# ST1-1-Top.net
KiCad netlist of a schematic drawn in Altium Designer
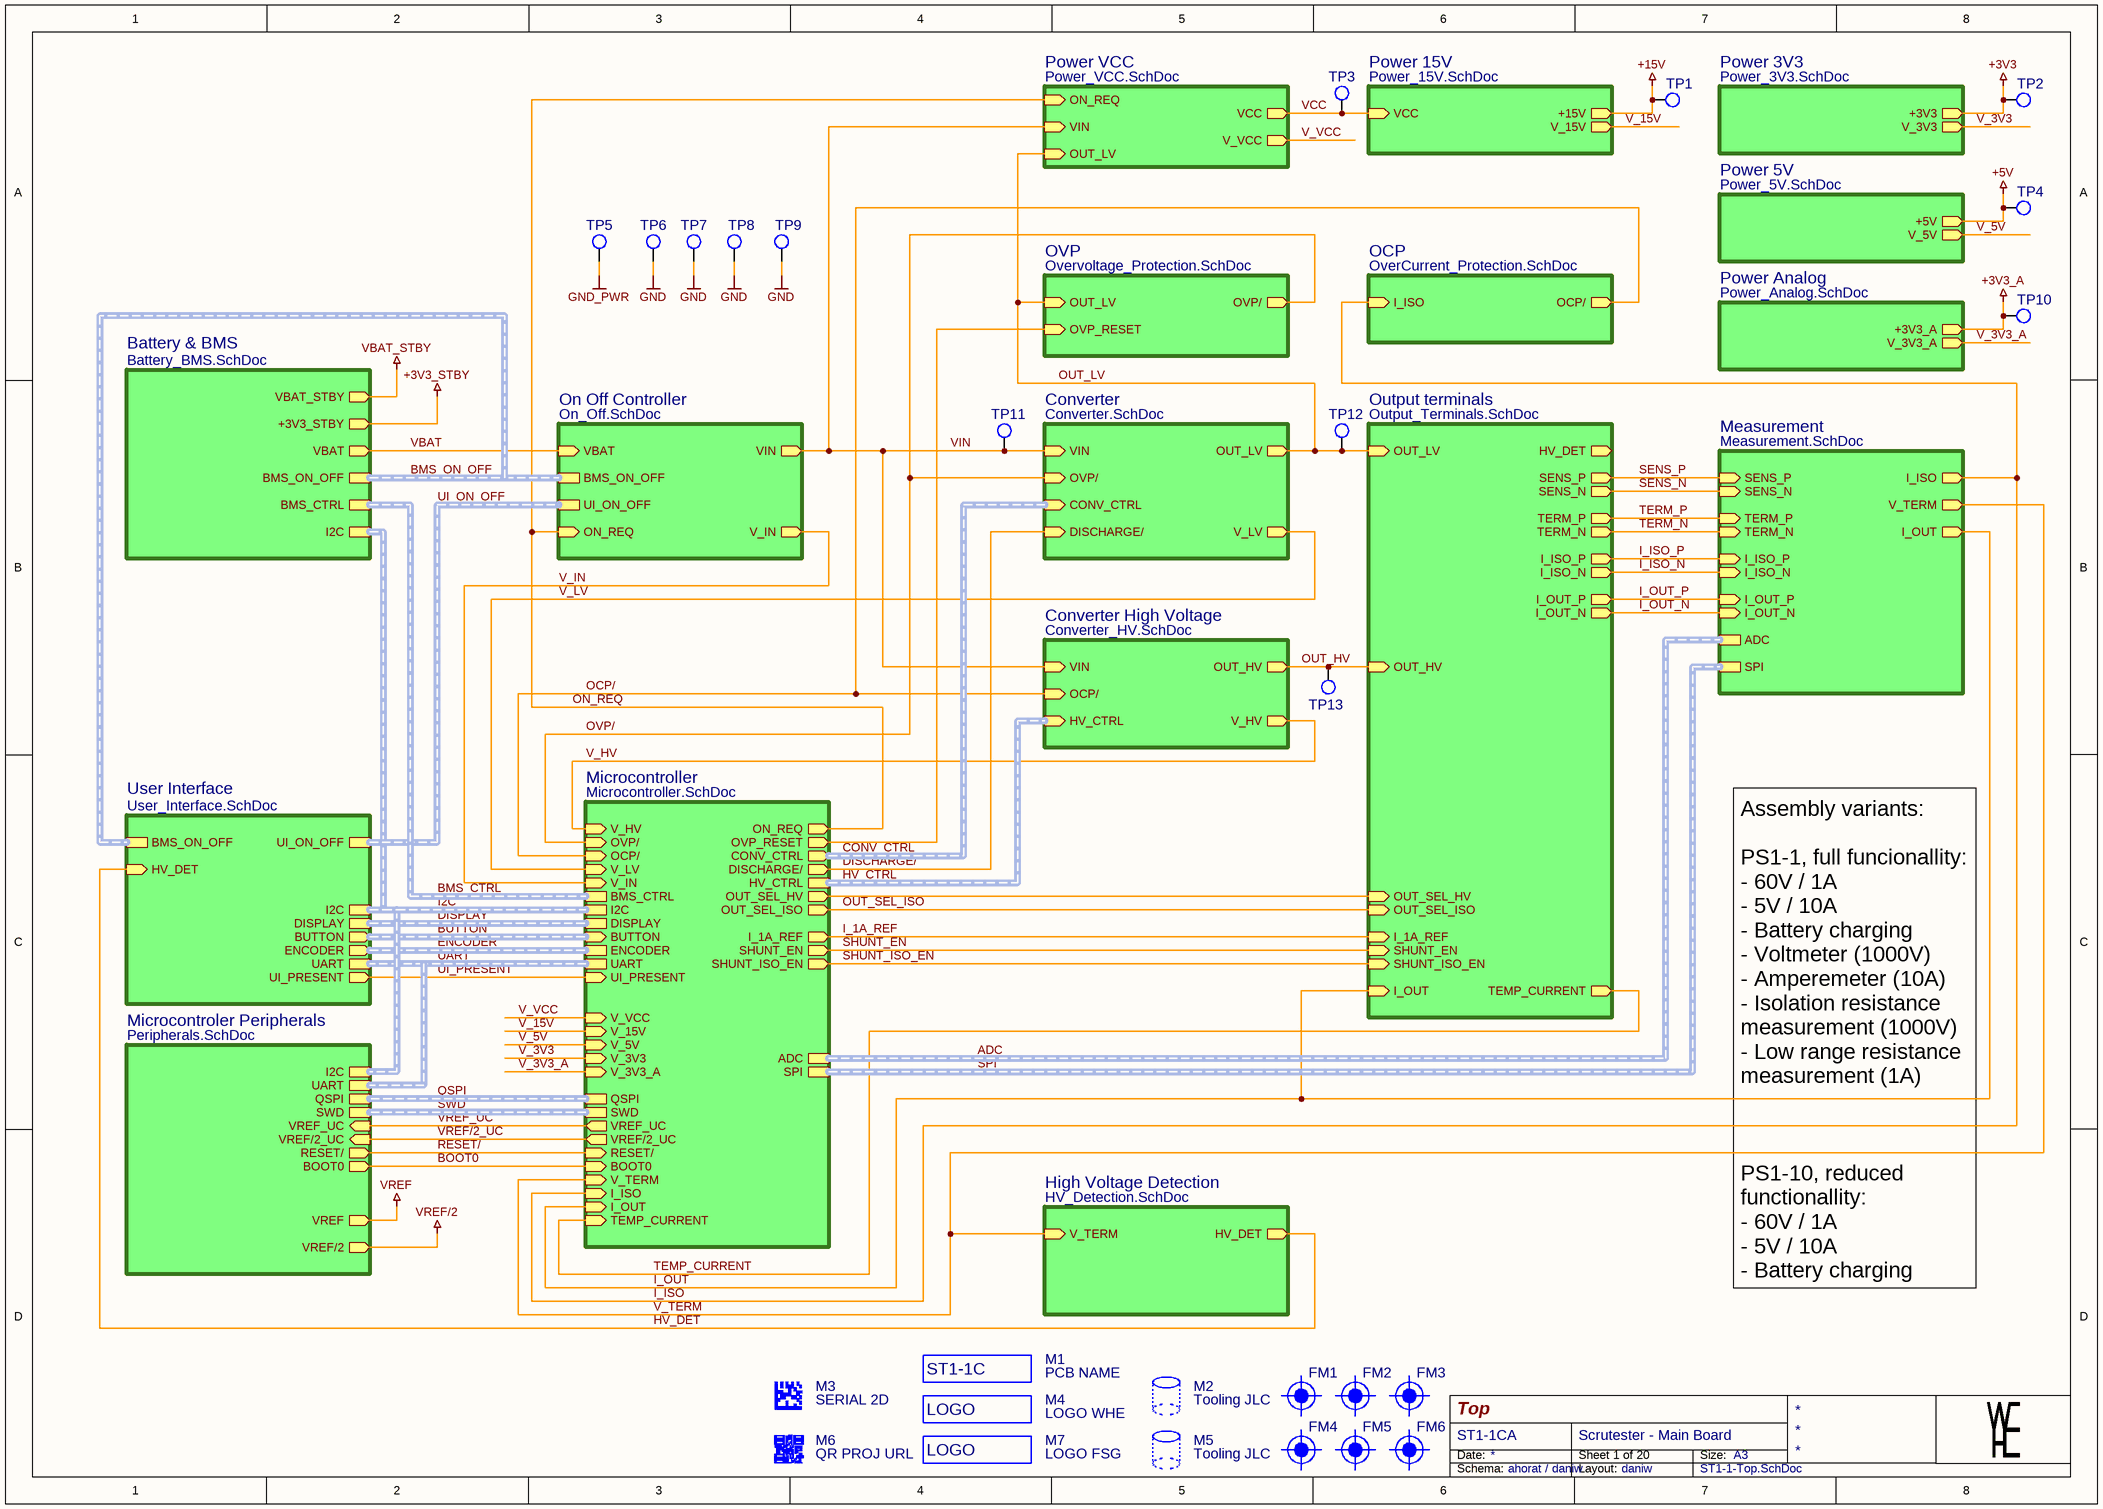
[diagram p0: ST1-1-Top.SchDoc]

(export (version "E")
  (design (tool "Eeschema 10.0.6"))
  (components
    (comp (ref "FM1")
      (value "Fidu")
      (footprint "FIDU-1MM")
      (description "Fiducial 1mm")
      (fields (field (name "PART NUMBER") "Fidu_1mm") (field (name "MANUFACTURER") "NONE"))
      (libsource (lib "daniw_altium_lib") (part "Fidu"))
    )
    (comp (ref "FM2")
      (value "Fidu")
      (footprint "FIDU-1MM")
      (description "Fiducial 1mm")
      (fields (field (name "PART NUMBER") "Fidu_1mm") (field (name "MANUFACTURER") "NONE"))
      (libsource (lib "daniw_altium_lib") (part "Fidu"))
    )
    (comp (ref "FM3")
      (value "Fidu")
      (footprint "FIDU-1MM")
      (description "Fiducial 1mm")
      (fields (field (name "PART NUMBER") "Fidu_1mm") (field (name "MANUFACTURER") "NONE"))
      (libsource (lib "daniw_altium_lib") (part "Fidu"))
    )
    (comp (ref "FM4")
      (value "Fidu")
      (footprint "FIDU-1MM")
      (description "Fiducial 1mm")
      (fields (field (name "PART NUMBER") "Fidu_1mm") (field (name "MANUFACTURER") "NONE"))
      (libsource (lib "daniw_altium_lib") (part "Fidu"))
    )
    (comp (ref "FM5")
      (value "Fidu")
      (footprint "FIDU-1MM")
      (description "Fiducial 1mm")
      (fields (field (name "PART NUMBER") "Fidu_1mm") (field (name "MANUFACTURER") "NONE"))
      (libsource (lib "daniw_altium_lib") (part "Fidu"))
    )
    (comp (ref "FM6")
      (value "Fidu")
      (footprint "FIDU-1MM")
      (description "Fiducial 1mm")
      (fields (field (name "PART NUMBER") "Fidu_1mm") (field (name "MANUFACTURER") "NONE"))
      (libsource (lib "daniw_altium_lib") (part "Fidu"))
    )
    (comp (ref "M1")
      (value "PCB NAME")
      (footprint "PCB-NAME-5MM-LEFT")
      (description "PCB name, 5mm text height, left-aligned")
      (fields (field (name "PART NUMBER") "PCB NAME 5mm L") (field (name "MANUFACTURER") "NONE"))
      (libsource (lib "daniw_altium_lib") (part "PCB-NAME"))
    )
    (comp (ref "M2")
      (value "Tooling JLC")
      (footprint "TOOLING-JLC")
      (description "Tooling hole for JLC (1.152mm)")
      (fields (field (name "MANUFACTURER") "NONE"))
      (libsource (lib "daniw_altium_lib") (part "HOLE"))
    )
    (comp (ref "M3")
      (value "SERIAL 2D")
      (footprint "SERIAL-2D-10MM-RESTRICT")
      (description "2D Serial number placeholder, Dotmatrix or QR, size: 10mm, restriction on top layer")
      (fields (field (name "PART NUMBER") "SERIAL 2D 10MM RESTRICT") (field (name "MANUFACTURER") "NONE"))
      (libsource (lib "daniw_altium_lib") (part "SERIAL-2D"))
    )
    (comp (ref "M4")
      (value "LOGO WHE")
      (footprint "LOGO-WHE-10MM")
      (description "WHE logo, size 10mm")
      (fields (field (name "PART NUMBER") "LOGO WHE 10MM") (field (name "MANUFACTURER") "NONE"))
      (libsource (lib "daniw_altium_lib") (part "LOGO"))
    )
    (comp (ref "M5")
      (value "Tooling JLC")
      (footprint "TOOLING-JLC")
      (description "Tooling hole for JLC (1.152mm)")
      (fields (field (name "MANUFACTURER") "NONE"))
      (libsource (lib "daniw_altium_lib") (part "HOLE"))
    )
    (comp (ref "M6")
      (value "QR PROJ URL")
      (footprint "QR-PROJECT-URL-10MM")
      (description "QR Code, Project URL, 10mm")
      (fields (field (name "PART NUMBER") "QR PROJ URL 10MM") (field (name "MANUFACTURER") "NONE"))
      (libsource (lib "daniw_altium_lib") (part "QR-PROJ-URL"))
    )
    (comp (ref "M7")
      (value "LOGO FSG")
      (footprint "LOGO-FSG-10MM")
      (description "FSG logo, size 10mm")
      (fields (field (name "PART NUMBER") "LOGO FSG 10MM") (field (name "MANUFACTURER") "NONE"))
      (libsource (lib "daniw_altium_lib") (part "LOGO"))
    )
    (comp (ref "TP1")
      (value "TP_THD_1.5/0.8")
      (footprint "TP_THD_1.5/0.8")
      (description "THT Test Point 1.5/0.8mm")
      (fields (field (name "MANUFACTURER") "NONE"))
      (libsource (lib "daniw_altium_lib") (part "Testpoint"))
    )
    (comp (ref "TP2")
      (value "TP_THD_1.5/0.8")
      (footprint "TP_THD_1.5/0.8")
      (description "THT Test Point 1.5/0.8mm")
      (fields (field (name "MANUFACTURER") "NONE"))
      (libsource (lib "daniw_altium_lib") (part "Testpoint"))
    )
    (comp (ref "TP3")
      (value "TP_THD_1.5/0.8")
      (footprint "TP_THD_1.5/0.8")
      (description "THT Test Point 1.5/0.8mm")
      (fields (field (name "MANUFACTURER") "NONE"))
      (libsource (lib "daniw_altium_lib") (part "Testpoint"))
    )
    (comp (ref "TP4")
      (value "TP_THD_1.5/0.8")
      (footprint "TP_THD_1.5/0.8")
      (description "THT Test Point 1.5/0.8mm")
      (fields (field (name "MANUFACTURER") "NONE"))
      (libsource (lib "daniw_altium_lib") (part "Testpoint"))
    )
    (comp (ref "TP5")
      (value "TP_THD_1.5/0.8")
      (footprint "TP_THD_1.5/0.8")
      (description "THT Test Point 1.5/0.8mm")
      (fields (field (name "MANUFACTURER") "NONE"))
      (libsource (lib "daniw_altium_lib") (part "Testpoint"))
    )
    (comp (ref "TP6")
      (value "TP_THD_1.5/0.8")
      (footprint "TP_THD_1.5/0.8")
      (description "THT Test Point 1.5/0.8mm")
      (fields (field (name "MANUFACTURER") "NONE"))
      (libsource (lib "daniw_altium_lib") (part "Testpoint"))
    )
    (comp (ref "TP7")
      (value "TP_THD_1.5/0.8")
      (footprint "TP_THD_1.5/0.8")
      (description "THT Test Point 1.5/0.8mm")
      (fields (field (name "MANUFACTURER") "NONE"))
      (libsource (lib "daniw_altium_lib") (part "Testpoint"))
    )
    (comp (ref "TP8")
      (value "TP_THD_1.5/0.8")
      (footprint "TP_THD_1.5/0.8")
      (description "THT Test Point 1.5/0.8mm")
      (fields (field (name "MANUFACTURER") "NONE"))
      (libsource (lib "daniw_altium_lib") (part "Testpoint"))
    )
    (comp (ref "TP9")
      (value "TP_THD_1.5/0.8")
      (footprint "TP_THD_1.5/0.8")
      (description "THT Test Point 1.5/0.8mm")
      (fields (field (name "MANUFACTURER") "NONE"))
      (libsource (lib "daniw_altium_lib") (part "Testpoint"))
    )
    (comp (ref "TP10")
      (value "TP_THD_1.5/0.8")
      (footprint "TP_THD_1.5/0.8")
      (description "THT Test Point 1.5/0.8mm")
      (fields (field (name "MANUFACTURER") "NONE"))
      (libsource (lib "daniw_altium_lib") (part "Testpoint"))
    )
    (comp (ref "TP11")
      (value "TP_THD_1.5/0.8")
      (footprint "TP_THD_1.5/0.8")
      (description "THT Test Point 1.5/0.8mm")
      (fields (field (name "MANUFACTURER") "NONE"))
      (libsource (lib "daniw_altium_lib") (part "Testpoint"))
    )
    (comp (ref "TP12")
      (value "TP_THD_1.5/0.8")
      (footprint "TP_THD_1.5/0.8")
      (description "THT Test Point 1.5/0.8mm")
      (fields (field (name "MANUFACTURER") "NONE"))
      (libsource (lib "daniw_altium_lib") (part "Testpoint"))
    )
    (comp (ref "TP13")
      (value "TP_THD_1.5/0.8")
      (footprint "TP_THD_1.5/0.8")
      (description "THT Test Point 1.5/0.8mm")
      (fields (field (name "MANUFACTURER") "NONE"))
      (libsource (lib "daniw_altium_lib") (part "Testpoint"))
    )
  )
  (nets
    (net (code "15") (name "+3V3") (class "Default")
      (node (ref "TP2") (pin "1") (pinfunction "1_1") (pintype "passive"))
    )
    (net (code "16") (name "+3V3_A") (class "Default")
      (node (ref "TP10") (pin "1") (pinfunction "1_1") (pintype "passive"))
    )
    (net (code "18") (name "+5V") (class "Default")
      (node (ref "TP4") (pin "1") (pinfunction "1_1") (pintype "passive"))
    )
    (net (code "19") (name "+15V") (class "Default")
      (node (ref "TP1") (pin "1") (pinfunction "1_1") (pintype "passive"))
    )
    (net (code "33") (name "/OUT_HV") (class "Default")
      (node (ref "TP13") (pin "1") (pinfunction "1_1") (pintype "passive"))
    )
    (net (code "34") (name "/OUT_LV") (class "Default")
      (node (ref "TP12") (pin "1") (pinfunction "1_1") (pintype "passive"))
    )
    (net (code "49") (name "/VCC") (class "Default")
      (node (ref "TP3") (pin "1") (pinfunction "1_1") (pintype "passive"))
    )
    (net (code "50") (name "/VIN") (class "Default")
      (node (ref "TP11") (pin "1") (pinfunction "1_1") (pintype "passive"))
    )
    (net (code "76") (name "GND") (class "Default")
      (node (ref "TP6") (pin "1") (pinfunction "1_1") (pintype "passive"))
      (node (ref "TP7") (pin "1") (pinfunction "1_1") (pintype "passive"))
      (node (ref "TP8") (pin "1") (pinfunction "1_1") (pintype "passive"))
      (node (ref "TP9") (pin "1") (pinfunction "1_1") (pintype "passive"))
    )
    (net (code "77") (name "GND_PWR") (class "Default")
      (node (ref "TP5") (pin "1") (pinfunction "1_1") (pintype "passive"))
    )
  )
)
